# ComparatorsWithVRef__LT6656.net
KiCad netlist of a schematic drawn in EAGLE
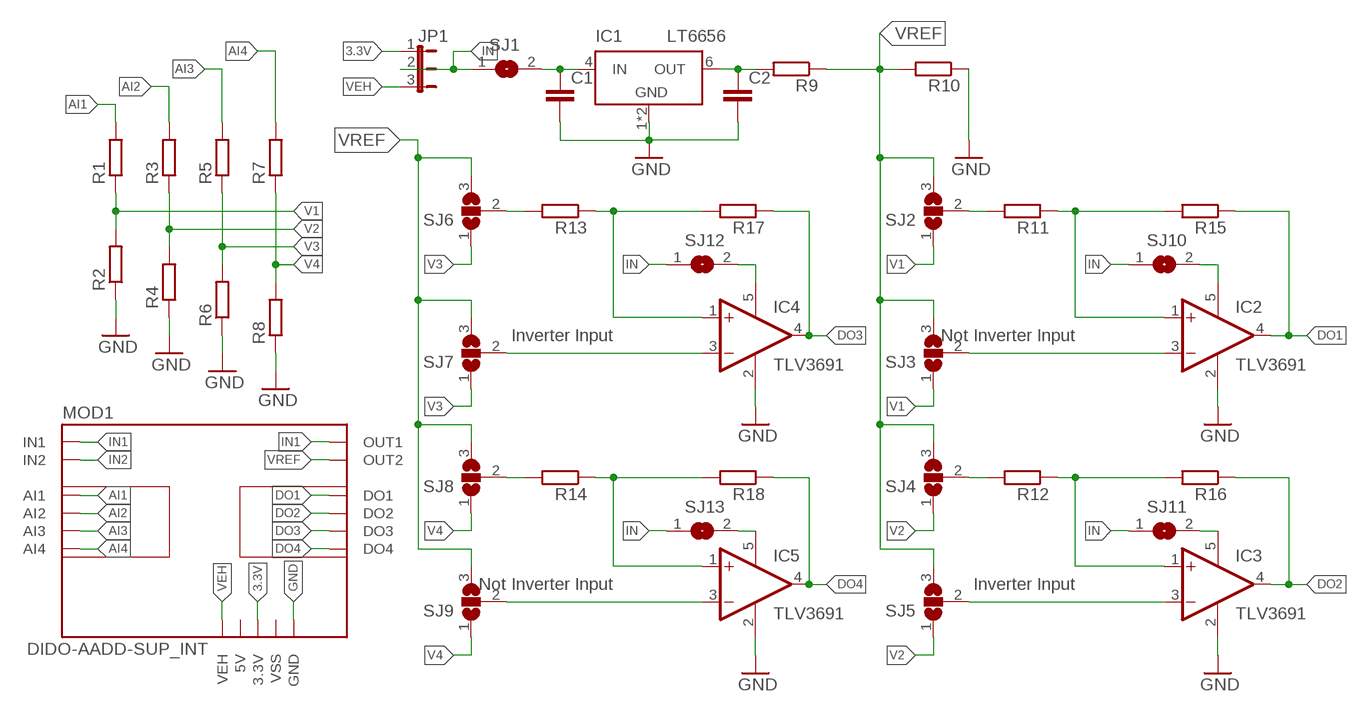
[diagram p0: schematic, sheet 1]

(export (version "E")
  (design (tool "Eeschema 10.0.6"))
  (components
    (comp (ref "C1")
      (value "0.1u")
      (footprint "eagle-import:C0805")
      (libsource (lib "eagle-import") (part "C-EUC0805"))
    )
    (comp (ref "C2")
      (value "1u")
      (footprint "eagle-import:C0805")
      (libsource (lib "eagle-import") (part "C-EUC0805"))
    )
    (comp (ref "IC1")
      (value "LT6656")
      (footprint "eagle-import:TSOT23-6")
      (libsource (lib "eagle-import") (part "LT6656"))
    )
    (comp (ref "IC2")
      (value "TLV3691")
      (footprint "eagle-import:DCK")
      (libsource (lib "eagle-import") (part "TLV3691"))
    )
    (comp (ref "IC3")
      (value "TLV3691")
      (footprint "eagle-import:DCK")
      (libsource (lib "eagle-import") (part "TLV3691"))
    )
    (comp (ref "IC4")
      (value "TLV3691")
      (footprint "eagle-import:DCK")
      (libsource (lib "eagle-import") (part "TLV3691"))
    )
    (comp (ref "IC5")
      (value "TLV3691")
      (footprint "eagle-import:DCK")
      (libsource (lib "eagle-import") (part "TLV3691"))
    )
    (comp (ref "JP1")
      (value "JP2E")
      (footprint "eagle-import:JP2")
      (libsource (lib "eagle-import") (part "JP2E"))
    )
    (comp (ref "MOD1")
      (value "DIDO-AADD-SUP_INT")
      (footprint "eagle-import:DIDO-AADD-SUP")
      (libsource (lib "eagle-import") (part "DIDO-AADD-SUP_INT"))
    )
    (comp (ref "R1")
      (value "R-EU_R0805")
      (footprint "eagle-import:R0805")
      (libsource (lib "eagle-import") (part "R-EU_R0805"))
    )
    (comp (ref "R2")
      (value "R-EU_R0805")
      (footprint "eagle-import:R0805")
      (libsource (lib "eagle-import") (part "R-EU_R0805"))
    )
    (comp (ref "R3")
      (value "R-EU_R0805")
      (footprint "eagle-import:R0805")
      (libsource (lib "eagle-import") (part "R-EU_R0805"))
    )
    (comp (ref "R4")
      (value "R-EU_R0805")
      (footprint "eagle-import:R0805")
      (libsource (lib "eagle-import") (part "R-EU_R0805"))
    )
    (comp (ref "R5")
      (value "R-EU_R0805")
      (footprint "eagle-import:R0805")
      (libsource (lib "eagle-import") (part "R-EU_R0805"))
    )
    (comp (ref "R6")
      (value "R-EU_R0805")
      (footprint "eagle-import:R0805")
      (libsource (lib "eagle-import") (part "R-EU_R0805"))
    )
    (comp (ref "R7")
      (value "R-EU_R0805")
      (footprint "eagle-import:R0805")
      (libsource (lib "eagle-import") (part "R-EU_R0805"))
    )
    (comp (ref "R8")
      (value "R-EU_R0805")
      (footprint "eagle-import:R0805")
      (libsource (lib "eagle-import") (part "R-EU_R0805"))
    )
    (comp (ref "R9")
      (value "R-EU_R0805")
      (footprint "eagle-import:R0805")
      (libsource (lib "eagle-import") (part "R-EU_R0805"))
    )
    (comp (ref "R10")
      (value "R-EU_R0805")
      (footprint "eagle-import:R0805")
      (libsource (lib "eagle-import") (part "R-EU_R0805"))
    )
    (comp (ref "R11")
      (value "R-EU_R0805")
      (footprint "eagle-import:R0805")
      (libsource (lib "eagle-import") (part "R-EU_R0805"))
    )
    (comp (ref "R12")
      (value "R-EU_R0805")
      (footprint "eagle-import:R0805")
      (libsource (lib "eagle-import") (part "R-EU_R0805"))
    )
    (comp (ref "R13")
      (value "R-EU_R0805")
      (footprint "eagle-import:R0805")
      (libsource (lib "eagle-import") (part "R-EU_R0805"))
    )
    (comp (ref "R14")
      (value "R-EU_R0805")
      (footprint "eagle-import:R0805")
      (libsource (lib "eagle-import") (part "R-EU_R0805"))
    )
    (comp (ref "R15")
      (value "R-EU_R0805")
      (footprint "eagle-import:R0805")
      (libsource (lib "eagle-import") (part "R-EU_R0805"))
    )
    (comp (ref "R16")
      (value "R-EU_R0805")
      (footprint "eagle-import:R0805")
      (libsource (lib "eagle-import") (part "R-EU_R0805"))
    )
    (comp (ref "R17")
      (value "R-EU_R0805")
      (footprint "eagle-import:R0805")
      (libsource (lib "eagle-import") (part "R-EU_R0805"))
    )
    (comp (ref "R18")
      (value "R-EU_R0805")
      (footprint "eagle-import:R0805")
      (libsource (lib "eagle-import") (part "R-EU_R0805"))
    )
    (comp (ref "SJ1") (value "SJ") (footprint "eagle-import:SJ") (libsource (lib "eagle-import") (part "SJ")))
    (comp (ref "SJ2")
      (value "SJ3")
      (footprint "eagle-import:SJ3")
      (libsource (lib "eagle-import") (part "SJ3"))
    )
    (comp (ref "SJ3")
      (value "SJ3")
      (footprint "eagle-import:SJ3")
      (libsource (lib "eagle-import") (part "SJ3"))
    )
    (comp (ref "SJ4")
      (value "SJ3")
      (footprint "eagle-import:SJ3")
      (libsource (lib "eagle-import") (part "SJ3"))
    )
    (comp (ref "SJ5")
      (value "SJ3")
      (footprint "eagle-import:SJ3")
      (libsource (lib "eagle-import") (part "SJ3"))
    )
    (comp (ref "SJ6")
      (value "SJ3")
      (footprint "eagle-import:SJ3")
      (libsource (lib "eagle-import") (part "SJ3"))
    )
    (comp (ref "SJ7")
      (value "SJ3")
      (footprint "eagle-import:SJ3")
      (libsource (lib "eagle-import") (part "SJ3"))
    )
    (comp (ref "SJ8")
      (value "SJ3")
      (footprint "eagle-import:SJ3")
      (libsource (lib "eagle-import") (part "SJ3"))
    )
    (comp (ref "SJ9")
      (value "SJ3")
      (footprint "eagle-import:SJ3")
      (libsource (lib "eagle-import") (part "SJ3"))
    )
    (comp (ref "SJ10")
      (value "SJ")
      (footprint "eagle-import:SJ")
      (libsource (lib "eagle-import") (part "SJ"))
    )
    (comp (ref "SJ11")
      (value "SJ")
      (footprint "eagle-import:SJ")
      (libsource (lib "eagle-import") (part "SJ"))
    )
    (comp (ref "SJ12")
      (value "SJ")
      (footprint "eagle-import:SJ")
      (libsource (lib "eagle-import") (part "SJ"))
    )
    (comp (ref "SJ13")
      (value "SJ")
      (footprint "eagle-import:SJ")
      (libsource (lib "eagle-import") (part "SJ"))
    )
  )
  (nets
    (net (code "1") (name "/5V") (class "Default")
      (node (ref "MOD1") (pin "5V") (pinfunction "5V_5V") (pintype "power_in"))
    )
    (net (code "2") (name "/VSS") (class "Default")
      (node (ref "MOD1") (pin "VSS") (pinfunction "VSS_VSS") (pintype "power_in"))
    )
    (net (code "3") (name "3.3V") (class "Default")
      (node (ref "JP1") (pin "1") (pinfunction "1_1") (pintype "passive"))
      (node (ref "MOD1") (pin "3.3V") (pinfunction "3.3V_3.3V") (pintype "power_in"))
    )
    (net (code "4") (name "AI1") (class "Default")
      (node (ref "MOD1") (pin "AI1") (pinfunction "AI1_AI1") (pintype "output"))
      (node (ref "R1") (pin "2") (pinfunction "2_2") (pintype "passive"))
    )
    (net (code "5") (name "AI2") (class "Default")
      (node (ref "MOD1") (pin "AI2") (pinfunction "AI2_AI2") (pintype "output"))
      (node (ref "R3") (pin "2") (pinfunction "2_2") (pintype "passive"))
    )
    (net (code "6") (name "AI3") (class "Default")
      (node (ref "MOD1") (pin "AI3") (pinfunction "AI3_AI3") (pintype "output"))
      (node (ref "R5") (pin "2") (pinfunction "2_2") (pintype "passive"))
    )
    (net (code "7") (name "AI4") (class "Default")
      (node (ref "MOD1") (pin "AI4") (pinfunction "AI4_AI4") (pintype "output"))
      (node (ref "R7") (pin "2") (pinfunction "2_2") (pintype "passive"))
    )
    (net (code "8") (name "DO1") (class "Default")
      (node (ref "IC2") (pin "4") (pinfunction "OUT_4") (pintype "output"))
      (node (ref "MOD1") (pin "DO1") (pinfunction "DO1_DO1") (pintype "output"))
      (node (ref "R15") (pin "1") (pinfunction "1_1") (pintype "passive"))
    )
    (net (code "9") (name "DO2") (class "Default")
      (node (ref "IC3") (pin "4") (pinfunction "OUT_4") (pintype "output"))
      (node (ref "MOD1") (pin "DO2") (pinfunction "DO2_DO2") (pintype "output"))
      (node (ref "R16") (pin "1") (pinfunction "1_1") (pintype "passive"))
    )
    (net (code "10") (name "DO3") (class "Default")
      (node (ref "IC4") (pin "4") (pinfunction "OUT_4") (pintype "output"))
      (node (ref "MOD1") (pin "DO3") (pinfunction "DO3_DO3") (pintype "output"))
      (node (ref "R17") (pin "1") (pinfunction "1_1") (pintype "passive"))
    )
    (net (code "11") (name "DO4") (class "Default")
      (node (ref "IC5") (pin "4") (pinfunction "OUT_4") (pintype "output"))
      (node (ref "MOD1") (pin "DO4") (pinfunction "DO4_DO4") (pintype "output"))
      (node (ref "R18") (pin "1") (pinfunction "1_1") (pintype "passive"))
    )
    (net (code "12") (name "GND") (class "Default")
      (node (ref "C1") (pin "2") (pinfunction "2_2") (pintype "passive"))
      (node (ref "C2") (pin "2") (pinfunction "2_2") (pintype "passive"))
      (node (ref "IC1") (pin "1") (pinfunction "GND_1") (pintype "power_in"))
      (node (ref "IC1") (pin "2") (pinfunction "GND_2") (pintype "power_in"))
      (node (ref "IC2") (pin "2") (pinfunction "V-_2") (pintype "power_in"))
      (node (ref "IC3") (pin "2") (pinfunction "V-_2") (pintype "power_in"))
      (node (ref "IC4") (pin "2") (pinfunction "V-_2") (pintype "power_in"))
      (node (ref "IC5") (pin "2") (pinfunction "V-_2") (pintype "power_in"))
      (node (ref "MOD1") (pin "GND1") (pinfunction "GND_GND1") (pintype "power_in"))
      (node (ref "MOD1") (pin "GND2") (pinfunction "GND_GND2") (pintype "power_in"))
      (node (ref "MOD1") (pin "GND3") (pinfunction "GND_GND3") (pintype "power_in"))
      (node (ref "MOD1") (pin "GND4") (pinfunction "GND_GND4") (pintype "power_in"))
      (node (ref "R10") (pin "1") (pinfunction "1_1") (pintype "passive"))
      (node (ref "R2") (pin "1") (pinfunction "1_1") (pintype "passive"))
      (node (ref "R4") (pin "1") (pinfunction "1_1") (pintype "passive"))
      (node (ref "R6") (pin "1") (pinfunction "1_1") (pintype "passive"))
      (node (ref "R8") (pin "1") (pinfunction "1_1") (pintype "passive"))
    )
    (net (code "13") (name "IN") (class "Default")
      (node (ref "JP1") (pin "2") (pinfunction "2_2") (pintype "passive"))
      (node (ref "SJ1") (pin "1") (pinfunction "1_1") (pintype "passive"))
      (node (ref "SJ10") (pin "1") (pinfunction "1_1") (pintype "passive"))
      (node (ref "SJ11") (pin "1") (pinfunction "1_1") (pintype "passive"))
      (node (ref "SJ12") (pin "1") (pinfunction "1_1") (pintype "passive"))
      (node (ref "SJ13") (pin "1") (pinfunction "1_1") (pintype "passive"))
    )
    (net (code "14") (name "IN1") (class "Default")
      (node (ref "MOD1") (pin "IN1") (pinfunction "IN1_IN1") (pintype "output"))
      (node (ref "MOD1") (pin "IN2") (pinfunction "IN1_IN2") (pintype "output"))
      (node (ref "MOD1") (pin "IN3") (pinfunction "IN1_IN3") (pintype "output"))
      (node (ref "MOD1") (pin "IN4") (pinfunction "IN1_IN4") (pintype "output"))
      (node (ref "MOD1") (pin "OUT1") (pinfunction "OUT1_OUT1") (pintype "input"))
      (node (ref "MOD1") (pin "OUT2") (pinfunction "OUT1_OUT2") (pintype "input"))
      (node (ref "MOD1") (pin "OUT3") (pinfunction "OUT1_OUT3") (pintype "input"))
      (node (ref "MOD1") (pin "OUT4") (pinfunction "OUT1_OUT4") (pintype "input"))
    )
    (net (code "15") (name "IN2") (class "Default")
      (node (ref "MOD1") (pin "IN2_1") (pinfunction "IN2_IN2_1") (pintype "output"))
      (node (ref "MOD1") (pin "IN2_2") (pinfunction "IN2_IN2_2") (pintype "output"))
      (node (ref "MOD1") (pin "IN2_3") (pinfunction "IN2_IN2_3") (pintype "output"))
      (node (ref "MOD1") (pin "IN2_4") (pinfunction "IN2_IN2_4") (pintype "output"))
    )
    (net (code "16") (name "Net-(IC1-IN)") (class "Default")
      (node (ref "C1") (pin "1") (pinfunction "1_1") (pintype "passive"))
      (node (ref "IC1") (pin "4") (pinfunction "IN_4") (pintype "input"))
      (node (ref "SJ1") (pin "2") (pinfunction "2_2") (pintype "passive"))
    )
    (net (code "17") (name "Net-(IC1-OUT)") (class "Default")
      (node (ref "C2") (pin "1") (pinfunction "1_1") (pintype "passive"))
      (node (ref "IC1") (pin "6") (pinfunction "OUT_6") (pintype "output"))
      (node (ref "R9") (pin "2") (pinfunction "2_2") (pintype "passive"))
    )
    (net (code "18") (name "Net-(IC2-+IN)") (class "Default")
      (node (ref "IC2") (pin "1") (pinfunction "+IN_1") (pintype "input"))
      (node (ref "R11") (pin "1") (pinfunction "1_1") (pintype "passive"))
      (node (ref "R15") (pin "2") (pinfunction "2_2") (pintype "passive"))
    )
    (net (code "19") (name "Net-(IC2--IN)") (class "Default")
      (node (ref "IC2") (pin "3") (pinfunction "-IN_3") (pintype "input"))
      (node (ref "SJ3") (pin "2") (pinfunction "2_2") (pintype "passive"))
    )
    (net (code "20") (name "Net-(IC2-V+)") (class "Default")
      (node (ref "IC2") (pin "5") (pinfunction "V+_5") (pintype "power_in"))
      (node (ref "SJ10") (pin "2") (pinfunction "2_2") (pintype "passive"))
    )
    (net (code "21") (name "Net-(IC3-+IN)") (class "Default")
      (node (ref "IC3") (pin "1") (pinfunction "+IN_1") (pintype "input"))
      (node (ref "R12") (pin "1") (pinfunction "1_1") (pintype "passive"))
      (node (ref "R16") (pin "2") (pinfunction "2_2") (pintype "passive"))
    )
    (net (code "22") (name "Net-(IC3--IN)") (class "Default")
      (node (ref "IC3") (pin "3") (pinfunction "-IN_3") (pintype "input"))
      (node (ref "SJ5") (pin "2") (pinfunction "2_2") (pintype "passive"))
    )
    (net (code "23") (name "Net-(IC3-V+)") (class "Default")
      (node (ref "IC3") (pin "5") (pinfunction "V+_5") (pintype "power_in"))
      (node (ref "SJ11") (pin "2") (pinfunction "2_2") (pintype "passive"))
    )
    (net (code "24") (name "Net-(IC4-+IN)") (class "Default")
      (node (ref "IC4") (pin "1") (pinfunction "+IN_1") (pintype "input"))
      (node (ref "R13") (pin "1") (pinfunction "1_1") (pintype "passive"))
      (node (ref "R17") (pin "2") (pinfunction "2_2") (pintype "passive"))
    )
    (net (code "25") (name "Net-(IC4--IN)") (class "Default")
      (node (ref "IC4") (pin "3") (pinfunction "-IN_3") (pintype "input"))
      (node (ref "SJ7") (pin "2") (pinfunction "2_2") (pintype "passive"))
    )
    (net (code "26") (name "Net-(IC4-V+)") (class "Default")
      (node (ref "IC4") (pin "5") (pinfunction "V+_5") (pintype "power_in"))
      (node (ref "SJ12") (pin "2") (pinfunction "2_2") (pintype "passive"))
    )
    (net (code "27") (name "Net-(IC5-+IN)") (class "Default")
      (node (ref "IC5") (pin "1") (pinfunction "+IN_1") (pintype "input"))
      (node (ref "R14") (pin "1") (pinfunction "1_1") (pintype "passive"))
      (node (ref "R18") (pin "2") (pinfunction "2_2") (pintype "passive"))
    )
    (net (code "28") (name "Net-(IC5--IN)") (class "Default")
      (node (ref "IC5") (pin "3") (pinfunction "-IN_3") (pintype "input"))
      (node (ref "SJ9") (pin "2") (pinfunction "2_2") (pintype "passive"))
    )
    (net (code "29") (name "Net-(IC5-V+)") (class "Default")
      (node (ref "IC5") (pin "5") (pinfunction "V+_5") (pintype "power_in"))
      (node (ref "SJ13") (pin "2") (pinfunction "2_2") (pintype "passive"))
    )
    (net (code "30") (name "Net-(R11-Pad2)") (class "Default")
      (node (ref "R11") (pin "2") (pinfunction "2_2") (pintype "passive"))
      (node (ref "SJ2") (pin "2") (pinfunction "2_2") (pintype "passive"))
    )
    (net (code "31") (name "Net-(R12-Pad2)") (class "Default")
      (node (ref "R12") (pin "2") (pinfunction "2_2") (pintype "passive"))
      (node (ref "SJ4") (pin "2") (pinfunction "2_2") (pintype "passive"))
    )
    (net (code "32") (name "Net-(R13-Pad2)") (class "Default")
      (node (ref "R13") (pin "2") (pinfunction "2_2") (pintype "passive"))
      (node (ref "SJ6") (pin "2") (pinfunction "2_2") (pintype "passive"))
    )
    (net (code "33") (name "Net-(R14-Pad2)") (class "Default")
      (node (ref "R14") (pin "2") (pinfunction "2_2") (pintype "passive"))
      (node (ref "SJ8") (pin "2") (pinfunction "2_2") (pintype "passive"))
    )
    (net (code "34") (name "V1") (class "Default")
      (node (ref "R1") (pin "1") (pinfunction "1_1") (pintype "passive"))
      (node (ref "R2") (pin "2") (pinfunction "2_2") (pintype "passive"))
      (node (ref "SJ2") (pin "1") (pinfunction "1_1") (pintype "passive"))
      (node (ref "SJ3") (pin "1") (pinfunction "1_1") (pintype "passive"))
    )
    (net (code "35") (name "V2") (class "Default")
      (node (ref "R3") (pin "1") (pinfunction "1_1") (pintype "passive"))
      (node (ref "R4") (pin "2") (pinfunction "2_2") (pintype "passive"))
      (node (ref "SJ4") (pin "1") (pinfunction "1_1") (pintype "passive"))
      (node (ref "SJ5") (pin "1") (pinfunction "1_1") (pintype "passive"))
    )
    (net (code "36") (name "V3") (class "Default")
      (node (ref "R5") (pin "1") (pinfunction "1_1") (pintype "passive"))
      (node (ref "R6") (pin "2") (pinfunction "2_2") (pintype "passive"))
      (node (ref "SJ6") (pin "1") (pinfunction "1_1") (pintype "passive"))
      (node (ref "SJ7") (pin "1") (pinfunction "1_1") (pintype "passive"))
    )
    (net (code "37") (name "V4") (class "Default")
      (node (ref "R7") (pin "1") (pinfunction "1_1") (pintype "passive"))
      (node (ref "R8") (pin "2") (pinfunction "2_2") (pintype "passive"))
      (node (ref "SJ8") (pin "1") (pinfunction "1_1") (pintype "passive"))
      (node (ref "SJ9") (pin "1") (pinfunction "1_1") (pintype "passive"))
    )
    (net (code "38") (name "VEH") (class "Default")
      (node (ref "JP1") (pin "3") (pinfunction "3_3") (pintype "passive"))
      (node (ref "MOD1") (pin "VEH") (pinfunction "VEH_VEH") (pintype "power_in"))
    )
    (net (code "39") (name "VREF") (class "Default")
      (node (ref "MOD1") (pin "OUT2_1") (pinfunction "OUT2_OUT2_1") (pintype "input"))
      (node (ref "MOD1") (pin "OUT2_2") (pinfunction "OUT2_OUT2_2") (pintype "input"))
      (node (ref "MOD1") (pin "OUT2_3") (pinfunction "OUT2_OUT2_3") (pintype "input"))
      (node (ref "MOD1") (pin "OUT2_4") (pinfunction "OUT2_OUT2_4") (pintype "input"))
      (node (ref "R10") (pin "2") (pinfunction "2_2") (pintype "passive"))
      (node (ref "R9") (pin "1") (pinfunction "1_1") (pintype "passive"))
      (node (ref "SJ2") (pin "3") (pinfunction "3_3") (pintype "passive"))
      (node (ref "SJ3") (pin "3") (pinfunction "3_3") (pintype "passive"))
      (node (ref "SJ4") (pin "3") (pinfunction "3_3") (pintype "passive"))
      (node (ref "SJ5") (pin "3") (pinfunction "3_3") (pintype "passive"))
      (node (ref "SJ6") (pin "3") (pinfunction "3_3") (pintype "passive"))
      (node (ref "SJ7") (pin "3") (pinfunction "3_3") (pintype "passive"))
      (node (ref "SJ8") (pin "3") (pinfunction "3_3") (pintype "passive"))
      (node (ref "SJ9") (pin "3") (pinfunction "3_3") (pintype "passive"))
    )
  )
)
